# schematic.net
KiCad netlist of a schematic drawn in Altium Designer
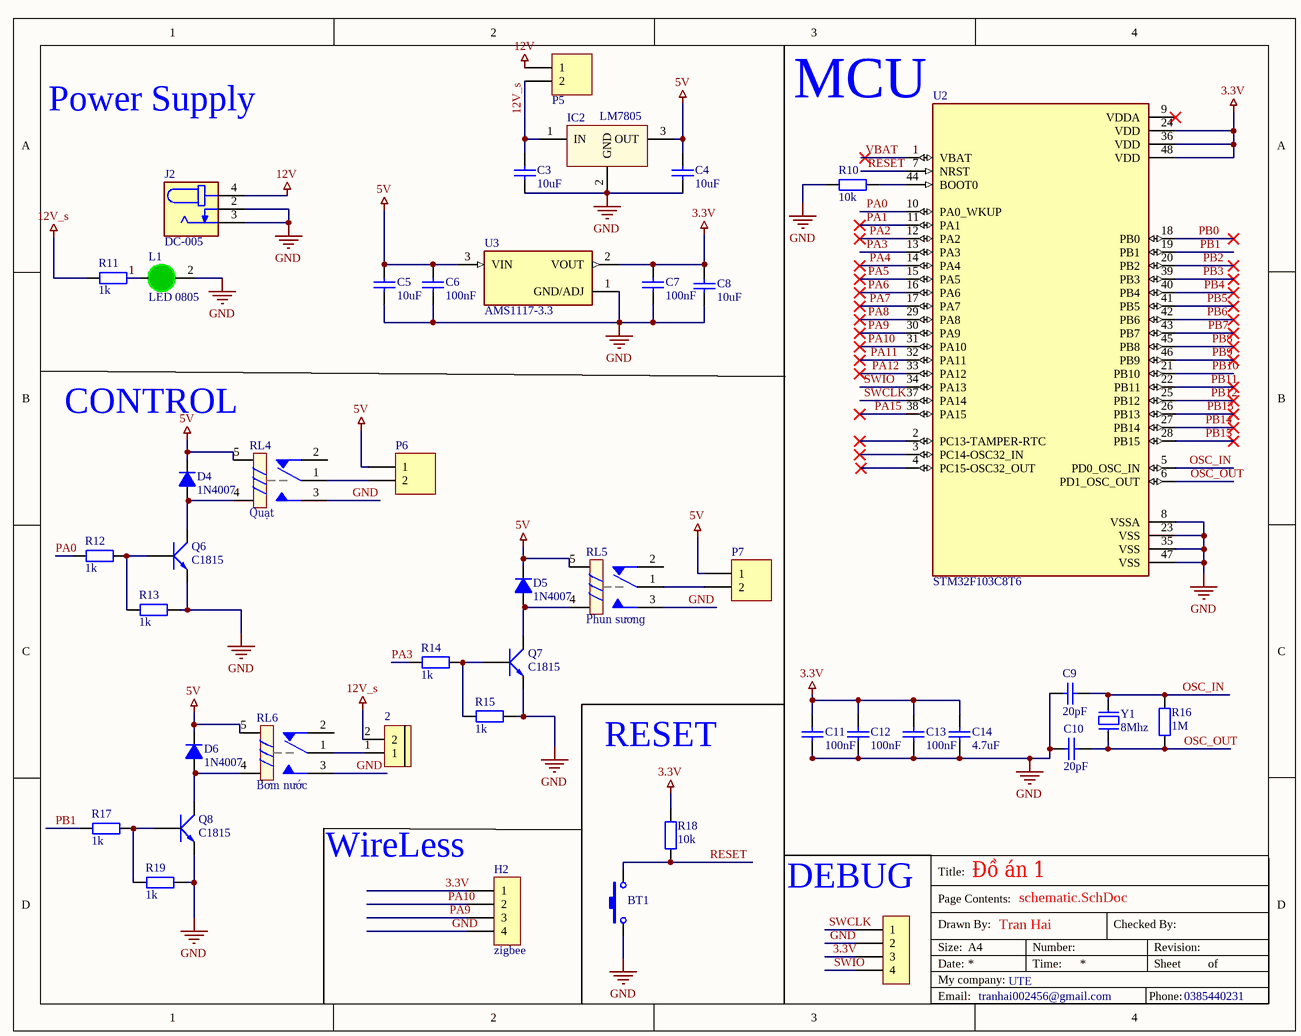
[diagram p0: schematic.SchDoc]

(export (version "E")
  (design (tool "Eeschema 10.0.6"))
  (components
    (comp (ref "2")
      (value "CON 2 KF301")
      (footprint "Con 2 KF301 5.08")
      (description "Cắm")
      (libsource (lib "Altium_Lib_by_KhueNguyenCreator") (part "CON 2 KF301"))
    )
    (comp (ref "BT1")
      (value "Nut Nhan 2 Chan SMD 3x6x2.5")
      (footprint "Nut Nhan 2 Chan SMD 3x6x2.5")
      (libsource (lib "Altium_Lib_by_KhueNguyenCreator") (part "Nut Nhan 2 Chan SMD 3x6x2.5"))
    )
    (comp (ref "C3")
      (value "10uF")
      (footprint "tu 0805")
      (description "Dán")
      (libsource (lib "Altium_Lib_by_KhueNguyenCreator") (part "Tu 0805 101 50V 20%"))
    )
    (comp (ref "C4")
      (value "10uF")
      (footprint "tu 0805")
      (description "Dán")
      (libsource (lib "Altium_Lib_by_KhueNguyenCreator") (part "Tu 0805 101 50V 20%"))
    )
    (comp (ref "C5")
      (value "10uF")
      (footprint "Tu 0805")
      (description "Dán")
      (libsource (lib "Altium_Lib_by_KhueNguyenCreator") (part "Tu 0805 200pF 50V 10%"))
    )
    (comp (ref "C6")
      (value "100nF")
      (footprint "Tu 0805")
      (description "Dán")
      (libsource (lib "Altium_Lib_by_KhueNguyenCreator") (part "Tu 0805 200pF 50V 10%"))
    )
    (comp (ref "C7")
      (value "100nF")
      (footprint "Tu 0805")
      (description "Dán")
      (libsource (lib "Altium_Lib_by_KhueNguyenCreator") (part "Tu 0805 200pF 50V 10%"))
    )
    (comp (ref "C8")
      (value "10uF")
      (footprint "Tu 0805")
      (description "Dán")
      (libsource (lib "Altium_Lib_by_KhueNguyenCreator") (part "Tu 0805 200pF 50V 10%"))
    )
    (comp (ref "C9")
      (value "20pF")
      (footprint "tu 0805")
      (description "Dán")
      (libsource (lib "Altium_Lib_by_KhueNguyenCreator") (part "Tu 0805 101 50V 20%"))
    )
    (comp (ref "C10")
      (value "20pF")
      (footprint "tu 0805")
      (description "Dán")
      (libsource (lib "Altium_Lib_by_KhueNguyenCreator") (part "Tu 0805 101 50V 20%"))
    )
    (comp (ref "C11")
      (value "100nF")
      (footprint "tu 0805")
      (description "Dán")
      (libsource (lib "") (part "Tu 0805 101 50V 20%_1"))
    )
    (comp (ref "C12")
      (value "100nF")
      (footprint "tu 0805")
      (description "Dán")
      (libsource (lib "") (part "Tu 0805 101 50V 20%_1"))
    )
    (comp (ref "C13")
      (value "100nF")
      (footprint "tu 0805")
      (description "Dán")
      (libsource (lib "") (part "Tu 0805 101 50V 20%_1"))
    )
    (comp (ref "C14")
      (value "4.7uF")
      (footprint "tu 0805")
      (description "Dán")
      (libsource (lib "") (part "Tu 0805 101 50V 20%_1"))
    )
    (comp (ref "D4")
      (value "1N4007")
      (footprint "D1A")
      (description "Diode 1A")
      (libsource (lib "Library AL") (part "D1A"))
    )
    (comp (ref "D5")
      (value "1N4007")
      (footprint "D1A")
      (description "Diode 1A")
      (libsource (lib "Library AL") (part "D1A"))
    )
    (comp (ref "D6")
      (value "1N4007")
      (footprint "D1A")
      (description "Diode 1A")
      (libsource (lib "Library AL") (part "D1A"))
    )
    (comp (ref "H2")
      (value "zigbee")
      (footprint "XH2.54M-4")
      (description "Cắm")
      (libsource (lib "Altium_Lib_by_KhueNguyenCreator") (part "Header 4P 2.54 Duc Thang"))
    )
    (comp (ref "H3")
      (value "Header 4P 2.54 Duc Thang")
      (footprint "XH2.54M-4")
      (description "Cắm")
      (libsource (lib "Altium_Lib_by_KhueNguyenCreator") (part "Header 4P 2.54 Duc Thang"))
    )
    (comp (ref "IC2")
      (value "LM7805")
      (footprint "QTO-220")
      (description "On ap +, from + 5 to + 24VDC")
      (libsource (lib "Library AL") (part "LM78xx"))
    )
    (comp (ref "J2")
      (value "DC-005")
      (footprint "NINIGI_DC-005")
      (description "DC Jack")
      (libsource (lib "DC-005") (part "DC-005"))
    )
    (comp (ref "L1")
      (value "LED 0805")
      (footprint "LED-0805-Green")
      (description "Dán")
      (libsource (lib "Altium_Lib_by_KhueNguyenCreator") (part "LED 0805 Xanh La"))
    )
    (comp (ref "P5")
      (value "Header 2")
      (footprint "HDR1X2")
      (description "Header, 2-Pin")
      (libsource (lib "Library AL") (part "Header 2"))
    )
    (comp (ref "P6")
      (value "Header 2")
      (footprint "HDR1X2")
      (description "Header, 2-Pin")
      (fields (field (name "PUBLISHER") "Altium Limited"))
      (libsource (lib "Library AL") (part "Header 2"))
    )
    (comp (ref "P7")
      (value "Header 2")
      (footprint "HDR1X2")
      (description "Header, 2-Pin")
      (fields (field (name "PUBLISHER") "Altium Limited"))
      (libsource (lib "Library AL") (part "Header 2"))
    )
    (comp (ref "Q6")
      (value "C1815")
      (footprint "TO92")
      (description "NPN transistor")
      (libsource (lib "Altium_Lib_by_KhueNguyenCreator") (part "C1815"))
    )
    (comp (ref "Q7")
      (value "C1815")
      (footprint "TO92")
      (description "NPN transistor")
      (libsource (lib "Altium_Lib_by_KhueNguyenCreator") (part "C1815"))
    )
    (comp (ref "Q8")
      (value "C1815")
      (footprint "TO92")
      (description "NPN transistor")
      (libsource (lib "Altium_Lib_by_KhueNguyenCreator") (part "C1815"))
    )
    (comp (ref "R10")
      (value "10k")
      (footprint "tro smd 0805")
      (description "Dán")
      (libsource (lib "Altium_Lib_by_KhueNguyenCreator") (part "Tro 0805 1% 10k"))
    )
    (comp (ref "R11")
      (value "1k")
      (footprint "tro smd 0805")
      (description "Dán")
      (libsource (lib "Altium_Lib_by_KhueNguyenCreator") (part "Tro 0805 1% 10k"))
    )
    (comp (ref "R12")
      (value "1k")
      (footprint "R1/4W")
      (description "Resistor 1/4W")
      (libsource (lib "Library AL") (part "R1/4W"))
    )
    (comp (ref "R13")
      (value "1k")
      (footprint "R1/4W")
      (description "Resistor 1/4W")
      (libsource (lib "Library AL") (part "R1/4W"))
    )
    (comp (ref "R14")
      (value "1k")
      (footprint "R1/4W")
      (description "Resistor 1/4W")
      (libsource (lib "Library AL") (part "R1/4W"))
    )
    (comp (ref "R15")
      (value "1k")
      (footprint "R1/4W")
      (description "Resistor 1/4W")
      (libsource (lib "Library AL") (part "R1/4W"))
    )
    (comp (ref "R16")
      (value "1M")
      (footprint "tro smd 0805")
      (description "Dán")
      (libsource (lib "Altium_Lib_by_KhueNguyenCreator") (part "Tro 0805 1% 10k"))
    )
    (comp (ref "R17")
      (value "1k")
      (footprint "R1/4W")
      (description "Resistor 1/4W")
      (libsource (lib "Library AL") (part "R1/4W"))
    )
    (comp (ref "R18")
      (value "10k")
      (footprint "tro smd 0805")
      (description "Dán")
      (libsource (lib "Altium_Lib_by_KhueNguyenCreator") (part "Tro 0805 1% 10k"))
    )
    (comp (ref "R19")
      (value "1k")
      (footprint "R1/4W")
      (description "Resistor 1/4W")
      (libsource (lib "Library AL") (part "R1/4W"))
    )
    (comp (ref "RL4")
      (value "Quạt")
      (footprint "Relay 5 Chan SRD")
      (description "Relay 5 Chan")
      (libsource (lib "Altium_Lib_by_KhueNguyenCreator") (part "Relay 5 Chan SRD"))
    )
    (comp (ref "RL5")
      (value "Phun sương")
      (footprint "Relay 5 Chan SRD")
      (description "Relay 5 Chan")
      (libsource (lib "Altium_Lib_by_KhueNguyenCreator") (part "Relay 5 Chan SRD"))
    )
    (comp (ref "RL6")
      (value "Bơm nước")
      (footprint "Relay 5 Chan SRD")
      (description "Relay 5 Chan")
      (libsource (lib "Altium_Lib_by_KhueNguyenCreator") (part "Relay 5 Chan SRD"))
    )
    (comp (ref "U2")
      (value "STM32F103C8T6")
      (footprint "QFP50P900X900X160-48N")
      (description "ARM® Cortex®-M3 STM32F1 Microcontroller IC 32-Bit 72MHz 64KB (64K x 8) FLASH 48-LQFP (7x7)")
      (fields (field (name "MF") "STMicroelectronics"))
      (libsource (lib "STM32F103C8T6") (part "STM32F103C8T6"))
    )
    (comp (ref "U3")
      (value "AMS1117-3.3")
      (footprint "SOT229P700X180-4N")
      (description "Sot223/Pkg 1-Amp 3.3-Volt Low Drop Out Voltage Regulatator")
      (fields (field (name "MF") "Advanced Monolithic Systems"))
      (libsource (lib "AMS1117-3.3") (part "AMS1117-3.3"))
    )
    (comp (ref "Y1")
      (value "8Mhz")
      (footprint "Thach Anh 2 chan cam")
      (description "Crystal For all Crystal 2pin.")
      (libsource (lib "Altium_Lib_by_KhueNguyenCreator") (part "Thach Anh 2 chan Cam"))
    )
  )
  (nets
    (net (code "1") (name "/OSC_IN") (class "Default")
      (node (ref "C9") (pin "1") (pinfunction "1_1") (pintype "passive"))
      (node (ref "R16") (pin "2") (pinfunction "2_2") (pintype "passive"))
      (node (ref "U2") (pin "5") (pinfunction "PD0_OSC_IN_5") (pintype "bidirectional"))
      (node (ref "Y1") (pin "2") (pinfunction "2_2") (pintype "passive"))
    )
    (net (code "2") (name "/OSC_OUT") (class "Default")
      (node (ref "C10") (pin "1") (pinfunction "1_1") (pintype "passive"))
      (node (ref "R16") (pin "1") (pinfunction "1_1") (pintype "passive"))
      (node (ref "U2") (pin "6") (pinfunction "PD1_OSC_OUT_6") (pintype "bidirectional"))
      (node (ref "Y1") (pin "1") (pinfunction "1_1") (pintype "passive"))
    )
    (net (code "3") (name "/PA0") (class "Default")
      (node (ref "R12") (pin "1") (pinfunction "1_1") (pintype "passive"))
      (node (ref "U2") (pin "10") (pinfunction "PA0_WKUP_10") (pintype "bidirectional"))
    )
    (net (code "4") (name "/PA1") (class "Default")
      (node (ref "U2") (pin "11") (pinfunction "PA1_11") (pintype "bidirectional+no_connect"))
    )
    (net (code "5") (name "/PA2") (class "Default")
      (node (ref "U2") (pin "12") (pinfunction "PA2_12") (pintype "bidirectional+no_connect"))
    )
    (net (code "6") (name "/PA3") (class "Default")
      (node (ref "R14") (pin "1") (pinfunction "1_1") (pintype "passive"))
      (node (ref "U2") (pin "13") (pinfunction "PA3_13") (pintype "bidirectional"))
    )
    (net (code "7") (name "/PA4") (class "Default")
      (node (ref "U2") (pin "14") (pinfunction "PA4_14") (pintype "bidirectional+no_connect"))
    )
    (net (code "8") (name "/PA5") (class "Default")
      (node (ref "U2") (pin "15") (pinfunction "PA5_15") (pintype "bidirectional+no_connect"))
    )
    (net (code "9") (name "/PA6") (class "Default")
      (node (ref "U2") (pin "16") (pinfunction "PA6_16") (pintype "bidirectional+no_connect"))
    )
    (net (code "10") (name "/PA7") (class "Default")
      (node (ref "U2") (pin "17") (pinfunction "PA7_17") (pintype "bidirectional+no_connect"))
    )
    (net (code "11") (name "/PA8") (class "Default")
      (node (ref "U2") (pin "29") (pinfunction "PA8_29") (pintype "bidirectional+no_connect"))
    )
    (net (code "12") (name "/PA9") (class "Default")
      (node (ref "H2") (pin "3") (pinfunction "3_3") (pintype "passive"))
      (node (ref "U2") (pin "30") (pinfunction "PA9_30") (pintype "bidirectional"))
    )
    (net (code "13") (name "/PA10") (class "Default")
      (node (ref "H2") (pin "2") (pinfunction "2_2") (pintype "passive"))
      (node (ref "U2") (pin "31") (pinfunction "PA10_31") (pintype "bidirectional"))
    )
    (net (code "14") (name "/PA11") (class "Default")
      (node (ref "U2") (pin "32") (pinfunction "PA11_32") (pintype "bidirectional+no_connect"))
    )
    (net (code "15") (name "/PA12") (class "Default")
      (node (ref "U2") (pin "33") (pinfunction "PA12_33") (pintype "bidirectional+no_connect"))
    )
    (net (code "16") (name "/PA15") (class "Default")
      (node (ref "U2") (pin "38") (pinfunction "PA15_38") (pintype "bidirectional+no_connect"))
    )
    (net (code "17") (name "/PB0") (class "Default")
      (node (ref "U2") (pin "18") (pinfunction "PB0_18") (pintype "bidirectional+no_connect"))
    )
    (net (code "18") (name "/PB1") (class "Default")
      (node (ref "R17") (pin "1") (pinfunction "1_1") (pintype "passive"))
      (node (ref "U2") (pin "19") (pinfunction "PB1_19") (pintype "bidirectional"))
    )
    (net (code "19") (name "/PB2") (class "Default")
      (node (ref "U2") (pin "20") (pinfunction "PB2_20") (pintype "bidirectional+no_connect"))
    )
    (net (code "20") (name "/PB3") (class "Default")
      (node (ref "U2") (pin "39") (pinfunction "PB3_39") (pintype "bidirectional+no_connect"))
    )
    (net (code "21") (name "/PB4") (class "Default")
      (node (ref "U2") (pin "40") (pinfunction "PB4_40") (pintype "bidirectional+no_connect"))
    )
    (net (code "22") (name "/PB5") (class "Default")
      (node (ref "U2") (pin "41") (pinfunction "PB5_41") (pintype "bidirectional+no_connect"))
    )
    (net (code "23") (name "/PB6") (class "Default")
      (node (ref "U2") (pin "42") (pinfunction "PB6_42") (pintype "bidirectional+no_connect"))
    )
    (net (code "24") (name "/PB7") (class "Default")
      (node (ref "U2") (pin "43") (pinfunction "PB7_43") (pintype "bidirectional+no_connect"))
    )
    (net (code "25") (name "/PB8") (class "Default")
      (node (ref "U2") (pin "45") (pinfunction "PB8_45") (pintype "bidirectional+no_connect"))
    )
    (net (code "26") (name "/PB9") (class "Default")
      (node (ref "U2") (pin "46") (pinfunction "PB9_46") (pintype "bidirectional+no_connect"))
    )
    (net (code "27") (name "/PB10") (class "Default")
      (node (ref "U2") (pin "21") (pinfunction "PB10_21") (pintype "bidirectional"))
    )
    (net (code "28") (name "/PB11") (class "Default")
      (node (ref "U2") (pin "22") (pinfunction "PB11_22") (pintype "bidirectional+no_connect"))
    )
    (net (code "29") (name "/PB12") (class "Default")
      (node (ref "U2") (pin "25") (pinfunction "PB12_25") (pintype "bidirectional+no_connect"))
    )
    (net (code "30") (name "/PB13") (class "Default")
      (node (ref "U2") (pin "26") (pinfunction "PB13_26") (pintype "bidirectional+no_connect"))
    )
    (net (code "31") (name "/PB14") (class "Default")
      (node (ref "U2") (pin "27") (pinfunction "PB14_27") (pintype "bidirectional+no_connect"))
    )
    (net (code "32") (name "/PB15") (class "Default")
      (node (ref "U2") (pin "28") (pinfunction "PB15_28") (pintype "bidirectional+no_connect"))
    )
    (net (code "33") (name "/RESET") (class "Default")
      (node (ref "BT1") (pin "2") (pinfunction "2_2") (pintype "passive"))
      (node (ref "R18") (pin "1") (pinfunction "1_1") (pintype "passive"))
      (node (ref "U2") (pin "7") (pinfunction "NRST_7") (pintype "input"))
    )
    (net (code "34") (name "/SWCLK") (class "Default")
      (node (ref "H3") (pin "1") (pinfunction "1_1") (pintype "passive"))
      (node (ref "U2") (pin "37") (pinfunction "PA14_37") (pintype "bidirectional"))
    )
    (net (code "35") (name "/SWIO") (class "Default")
      (node (ref "H3") (pin "4") (pinfunction "4_4") (pintype "passive"))
      (node (ref "U2") (pin "34") (pinfunction "PA13_34") (pintype "bidirectional"))
    )
    (net (code "37") (name "/VBAT") (class "Default")
      (node (ref "U2") (pin "1") (pinfunction "VBAT_1") (pintype "bidirectional"))
    )
    (net (code "38") (name "3.3V") (class "Default")
      (node (ref "C11") (pin "1") (pinfunction "1_1") (pintype "passive"))
      (node (ref "C12") (pin "1") (pinfunction "1_1") (pintype "passive"))
      (node (ref "C13") (pin "1") (pinfunction "1_1") (pintype "passive"))
      (node (ref "C14") (pin "1") (pinfunction "1_1") (pintype "passive"))
      (node (ref "C7") (pin "1") (pinfunction "1_1") (pintype "passive"))
      (node (ref "C8") (pin "1") (pinfunction "1_1") (pintype "passive"))
      (node (ref "H2") (pin "1") (pinfunction "1_1") (pintype "passive"))
      (node (ref "H3") (pin "3") (pinfunction "3_3") (pintype "passive"))
      (node (ref "R18") (pin "2") (pinfunction "2_2") (pintype "passive"))
      (node (ref "U2") (pin "24") (pinfunction "VDD_24") (pintype "power_in"))
      (node (ref "U2") (pin "36") (pinfunction "VDD_36") (pintype "power_in"))
      (node (ref "U2") (pin "48") (pinfunction "VDD_48") (pintype "power_in"))
      (node (ref "U3") (pin "2") (pinfunction "VOUT_2") (pintype "output"))
    )
    (net (code "39") (name "5V") (class "Default")
      (node (ref "C4") (pin "1") (pinfunction "1_1") (pintype "passive"))
      (node (ref "C5") (pin "1") (pinfunction "1_1") (pintype "passive"))
      (node (ref "C6") (pin "1") (pinfunction "1_1") (pintype "passive"))
      (node (ref "D4") (pin "2") (pinfunction "K_2") (pintype "passive"))
      (node (ref "D5") (pin "2") (pinfunction "K_2") (pintype "passive"))
      (node (ref "D6") (pin "2") (pinfunction "K_2") (pintype "passive"))
      (node (ref "IC2") (pin "3") (pinfunction "OUT_3") (pintype "passive"))
      (node (ref "P6") (pin "1") (pinfunction "1_1") (pintype "passive"))
      (node (ref "P7") (pin "1") (pinfunction "1_1") (pintype "passive"))
      (node (ref "RL4") (pin "5") (pinfunction "5_5") (pintype "passive"))
      (node (ref "RL5") (pin "5") (pinfunction "5_5") (pintype "passive"))
      (node (ref "RL6") (pin "5") (pinfunction "5_5") (pintype "passive"))
      (node (ref "U3") (pin "3") (pinfunction "VIN_3") (pintype "input"))
    )
    (net (code "40") (name "12V") (class "Default")
      (node (ref "J2") (pin "4") (pinfunction "2_4") (pintype "passive"))
      (node (ref "P5") (pin "1") (pinfunction "1_1") (pintype "passive"))
    )
    (net (code "41") (name "12V_s") (class "Default")
      (node (ref "2") (pin "2") (pinfunction "2_2") (pintype "passive"))
      (node (ref "C3") (pin "1") (pinfunction "1_1") (pintype "passive"))
      (node (ref "IC2") (pin "1") (pinfunction "IN_1") (pintype "passive"))
      (node (ref "P5") (pin "2") (pinfunction "2_2") (pintype "passive"))
      (node (ref "R11") (pin "1") (pinfunction "1_1") (pintype "passive"))
    )
    (net (code "42") (name "GND") (class "Default")
      (node (ref "BT1") (pin "1") (pinfunction "1_1") (pintype "passive"))
      (node (ref "C10") (pin "2") (pinfunction "2_2") (pintype "passive"))
      (node (ref "C11") (pin "2") (pinfunction "2_2") (pintype "passive"))
      (node (ref "C12") (pin "2") (pinfunction "2_2") (pintype "passive"))
      (node (ref "C13") (pin "2") (pinfunction "2_2") (pintype "passive"))
      (node (ref "C14") (pin "2") (pinfunction "2_2") (pintype "passive"))
      (node (ref "C3") (pin "2") (pinfunction "2_2") (pintype "passive"))
      (node (ref "C4") (pin "2") (pinfunction "2_2") (pintype "passive"))
      (node (ref "C5") (pin "2") (pinfunction "2_2") (pintype "passive"))
      (node (ref "C6") (pin "2") (pinfunction "2_2") (pintype "passive"))
      (node (ref "C7") (pin "2") (pinfunction "2_2") (pintype "passive"))
      (node (ref "C8") (pin "2") (pinfunction "2_2") (pintype "passive"))
      (node (ref "C9") (pin "2") (pinfunction "2_2") (pintype "passive"))
      (node (ref "H2") (pin "4") (pinfunction "4_4") (pintype "passive"))
      (node (ref "H3") (pin "2") (pinfunction "2_2") (pintype "passive"))
      (node (ref "IC2") (pin "2") (pinfunction "GND_2") (pintype "passive"))
      (node (ref "J2") (pin "2") (pinfunction "4_2") (pintype "passive"))
      (node (ref "J2") (pin "3") (pinfunction "5_3") (pintype "passive"))
      (node (ref "L1") (pin "2") (pinfunction "K_2") (pintype "passive"))
      (node (ref "Q6") (pin "1") (pinfunction "E_1") (pintype "passive"))
      (node (ref "Q7") (pin "1") (pinfunction "E_1") (pintype "passive"))
      (node (ref "Q8") (pin "1") (pinfunction "E_1") (pintype "passive"))
      (node (ref "R10") (pin "1") (pinfunction "1_1") (pintype "passive"))
      (node (ref "R13") (pin "2") (pinfunction "2_2") (pintype "passive"))
      (node (ref "R15") (pin "2") (pinfunction "2_2") (pintype "passive"))
      (node (ref "R19") (pin "2") (pinfunction "2_2") (pintype "passive"))
      (node (ref "RL4") (pin "3") (pinfunction "3_3") (pintype "passive"))
      (node (ref "RL5") (pin "3") (pinfunction "3_3") (pintype "passive"))
      (node (ref "RL6") (pin "3") (pinfunction "3_3") (pintype "passive"))
      (node (ref "U2") (pin "23") (pinfunction "VSS_23") (pintype "power_in"))
      (node (ref "U2") (pin "35") (pinfunction "VSS_35") (pintype "power_in"))
      (node (ref "U2") (pin "47") (pinfunction "VSS_47") (pintype "power_in"))
      (node (ref "U2") (pin "8") (pinfunction "VSSA_8") (pintype "power_in"))
      (node (ref "U3") (pin "1") (pinfunction "GND/ADJ_1") (pintype "power_in"))
    )
    (net (code "43") (name "Net-(2-Pad1)") (class "Default")
      (node (ref "2") (pin "1") (pinfunction "1_1") (pintype "passive"))
      (node (ref "RL6") (pin "1") (pinfunction "1_1") (pintype "passive"))
    )
    (net (code "44") (name "Net-(D4-A)") (class "Default")
      (node (ref "D4") (pin "1") (pinfunction "A_1") (pintype "passive"))
      (node (ref "Q6") (pin "2") (pinfunction "C_2") (pintype "passive"))
      (node (ref "RL4") (pin "4") (pinfunction "4_4") (pintype "passive"))
    )
    (net (code "45") (name "Net-(D5-A)") (class "Default")
      (node (ref "D5") (pin "1") (pinfunction "A_1") (pintype "passive"))
      (node (ref "Q7") (pin "2") (pinfunction "C_2") (pintype "passive"))
      (node (ref "RL5") (pin "4") (pinfunction "4_4") (pintype "passive"))
    )
    (net (code "46") (name "Net-(D6-A)") (class "Default")
      (node (ref "D6") (pin "1") (pinfunction "A_1") (pintype "passive"))
      (node (ref "Q8") (pin "2") (pinfunction "C_2") (pintype "passive"))
      (node (ref "RL6") (pin "4") (pinfunction "4_4") (pintype "passive"))
    )
    (net (code "47") (name "Net-(L1-A)") (class "Default")
      (node (ref "L1") (pin "1") (pinfunction "A_1") (pintype "passive"))
      (node (ref "R11") (pin "2") (pinfunction "2_2") (pintype "passive"))
    )
    (net (code "48") (name "Net-(P6-Pad2)") (class "Default")
      (node (ref "P6") (pin "2") (pinfunction "2_2") (pintype "passive"))
      (node (ref "RL4") (pin "1") (pinfunction "1_1") (pintype "passive"))
    )
    (net (code "49") (name "Net-(P7-Pad2)") (class "Default")
      (node (ref "P7") (pin "2") (pinfunction "2_2") (pintype "passive"))
      (node (ref "RL5") (pin "1") (pinfunction "1_1") (pintype "passive"))
    )
    (net (code "50") (name "Net-(Q6-B)") (class "Default")
      (node (ref "Q6") (pin "3") (pinfunction "B_3") (pintype "passive"))
      (node (ref "R12") (pin "2") (pinfunction "2_2") (pintype "passive"))
      (node (ref "R13") (pin "1") (pinfunction "1_1") (pintype "passive"))
    )
    (net (code "51") (name "Net-(Q7-B)") (class "Default")
      (node (ref "Q7") (pin "3") (pinfunction "B_3") (pintype "passive"))
      (node (ref "R14") (pin "2") (pinfunction "2_2") (pintype "passive"))
      (node (ref "R15") (pin "1") (pinfunction "1_1") (pintype "passive"))
    )
    (net (code "52") (name "Net-(Q8-B)") (class "Default")
      (node (ref "Q8") (pin "3") (pinfunction "B_3") (pintype "passive"))
      (node (ref "R17") (pin "2") (pinfunction "2_2") (pintype "passive"))
      (node (ref "R19") (pin "1") (pinfunction "1_1") (pintype "passive"))
    )
    (net (code "53") (name "Net-(U2-BOOT0)") (class "Default")
      (node (ref "R10") (pin "2") (pinfunction "2_2") (pintype "passive"))
      (node (ref "U2") (pin "44") (pinfunction "BOOT0_44") (pintype "input"))
    )
    (net (code "54") (name "unconnected-(RL4-Pad2)") (class "Default")
      (node (ref "RL4") (pin "2") (pinfunction "2_2") (pintype "passive"))
    )
    (net (code "55") (name "unconnected-(RL5-Pad2)") (class "Default")
      (node (ref "RL5") (pin "2") (pinfunction "2_2") (pintype "passive"))
    )
    (net (code "56") (name "unconnected-(RL6-Pad2)") (class "Default")
      (node (ref "RL6") (pin "2") (pinfunction "2_2") (pintype "passive"))
    )
    (net (code "57") (name "unconnected-(U2-PC13-TAMPER-RTC-Pad2)") (class "Default")
      (node (ref "U2") (pin "2") (pinfunction "PC13-TAMPER-RTC_2") (pintype "bidirectional+no_connect"))
    )
    (net (code "58") (name "unconnected-(U2-PC14-OSC32_IN-Pad3)") (class "Default")
      (node (ref "U2") (pin "3") (pinfunction "PC14-OSC32_IN_3") (pintype "bidirectional+no_connect"))
    )
    (net (code "59") (name "unconnected-(U2-PC15-OSC32_OUT-Pad4)") (class "Default")
      (node (ref "U2") (pin "4") (pinfunction "PC15-OSC32_OUT_4") (pintype "bidirectional+no_connect"))
    )
    (net (code "60") (name "unconnected-(U2-VDDA-Pad9)") (class "Default")
      (node (ref "U2") (pin "9") (pinfunction "VDDA_9") (pintype "power_in+no_connect"))
    )
  )
)
